# pirmod.net
KiCad netlist of a schematic drawn in EAGLE
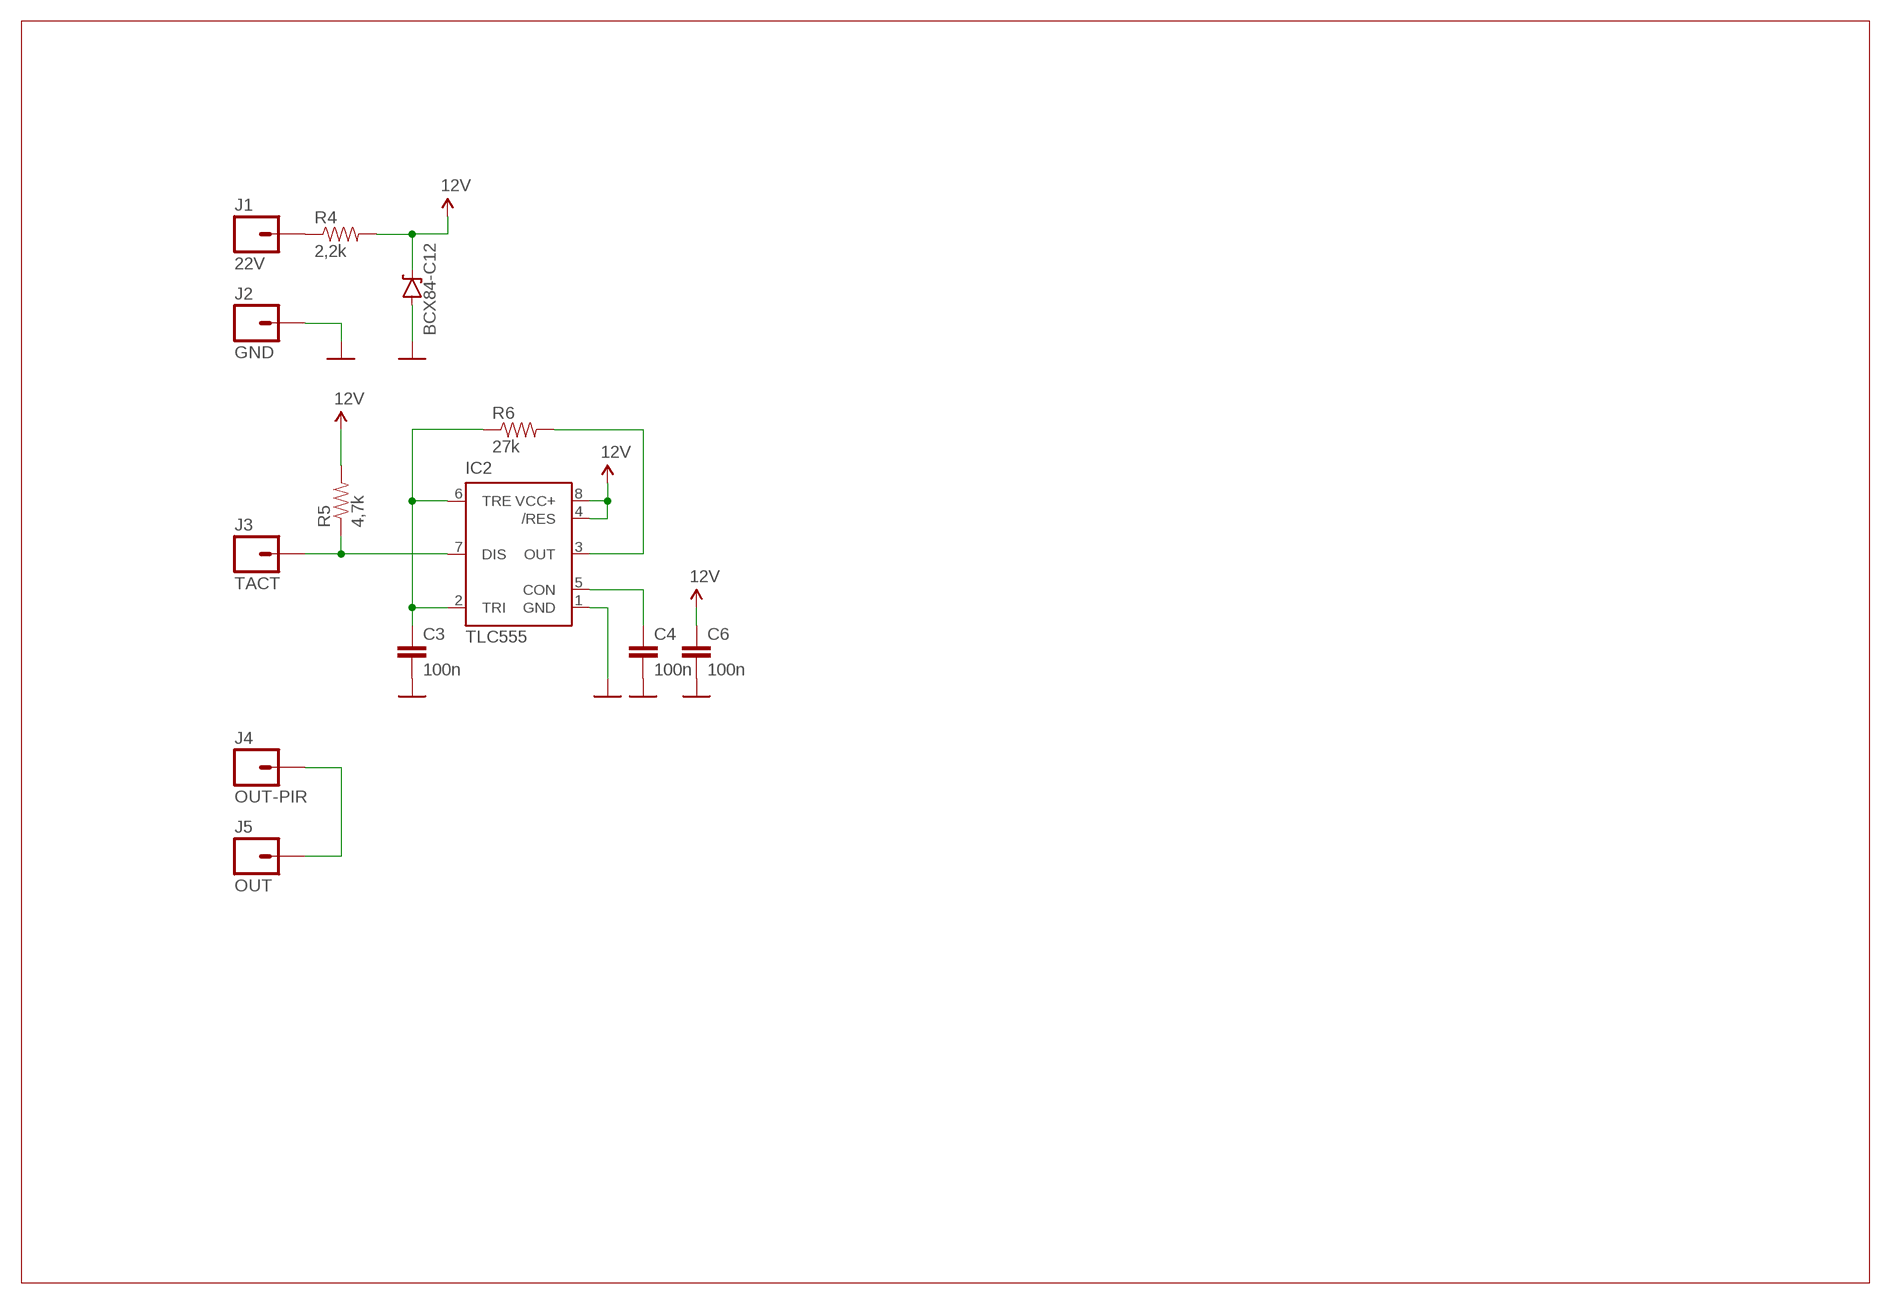
[diagram p0: schematic, sheet 1]

(export (version "E")
  (design (tool "Eeschema 10.0.6"))
  (components
    (comp (ref "C3")
      (value "100n")
      (footprint "eagle-import:0805")
      (libsource (lib "eagle-import") (part "CAP0805"))
    )
    (comp (ref "C4")
      (value "100n")
      (footprint "eagle-import:0805")
      (libsource (lib "eagle-import") (part "CAP0805"))
    )
    (comp (ref "C6")
      (value "100n")
      (footprint "eagle-import:0805")
      (libsource (lib "eagle-import") (part "CAP0805"))
    )
    (comp (ref "D2")
      (value "BCX84-C12")
      (footprint "eagle-import:SOT23-3")
      (libsource (lib "eagle-import") (part "DIODE-ZENER12V"))
    )
    (comp (ref "IC2")
      (value "TLC555")
      (footprint "eagle-import:SO08")
      (libsource (lib "eagle-import") (part "NE555D"))
    )
    (comp (ref "J1")
      (value "22V")
      (footprint "eagle-import:1X01")
      (libsource (lib "eagle-import") (part "M01PTH"))
    )
    (comp (ref "J2")
      (value "GND")
      (footprint "eagle-import:PAD-1.5X4.5")
      (libsource (lib "eagle-import") (part "M01SMD-4.5X1.5"))
    )
    (comp (ref "J3")
      (value "TACT")
      (footprint "eagle-import:1X01")
      (libsource (lib "eagle-import") (part "M01PTH"))
    )
    (comp (ref "J4")
      (value "OUT-PIR")
      (footprint "eagle-import:1X01")
      (libsource (lib "eagle-import") (part "M01PTH"))
    )
    (comp (ref "J5")
      (value "OUT")
      (footprint "eagle-import:1X01")
      (libsource (lib "eagle-import") (part "M01PTH"))
    )
    (comp (ref "R4")
      (value "2,2k")
      (footprint "eagle-import:0805")
      (libsource (lib "eagle-import") (part "RESISTOR0805-RES"))
    )
    (comp (ref "R5")
      (value "4,7k")
      (footprint "eagle-import:0805")
      (libsource (lib "eagle-import") (part "RESISTOR0805-RES"))
    )
    (comp (ref "R6")
      (value "27k")
      (footprint "eagle-import:0805")
      (libsource (lib "eagle-import") (part "RESISTOR0805-RES"))
    )
  )
  (nets
    (net (code "1") (name "12V") (class "Default")
      (node (ref "C6") (pin "1") (pinfunction "1_1") (pintype "passive"))
      (node (ref "D2") (pin "3") (pinfunction "C_3") (pintype "passive"))
      (node (ref "IC2") (pin "4") (pinfunction "/RES_4") (pintype "input"))
      (node (ref "IC2") (pin "8") (pinfunction "VCC+_8") (pintype "power_in"))
      (node (ref "R4") (pin "2") (pinfunction "2_2") (pintype "passive"))
      (node (ref "R5") (pin "2") (pinfunction "2_2") (pintype "passive"))
    )
    (net (code "2") (name "GND") (class "Default")
      (node (ref "C3") (pin "2") (pinfunction "2_2") (pintype "passive"))
      (node (ref "C4") (pin "2") (pinfunction "2_2") (pintype "passive"))
      (node (ref "C6") (pin "2") (pinfunction "2_2") (pintype "passive"))
      (node (ref "D2") (pin "1") (pinfunction "A_1") (pintype "passive"))
      (node (ref "IC2") (pin "1") (pinfunction "GND_1") (pintype "power_in"))
      (node (ref "J2") (pin "P$1") (pinfunction "1_P$1") (pintype "passive"))
    )
    (net (code "3") (name "Net-(IC2-CON)") (class "Default")
      (node (ref "C4") (pin "1") (pinfunction "1_1") (pintype "passive"))
      (node (ref "IC2") (pin "5") (pinfunction "CON_5") (pintype "input"))
    )
    (net (code "4") (name "Net-(IC2-DIS)") (class "Default")
      (node (ref "IC2") (pin "7") (pinfunction "DIS_7") (pintype "input"))
      (node (ref "J3") (pin "1") (pinfunction "1_1") (pintype "passive"))
      (node (ref "R5") (pin "1") (pinfunction "1_1") (pintype "passive"))
    )
    (net (code "5") (name "Net-(IC2-OUT)") (class "Default")
      (node (ref "IC2") (pin "3") (pinfunction "OUT_3") (pintype "output"))
      (node (ref "R6") (pin "2") (pinfunction "2_2") (pintype "passive"))
    )
    (net (code "6") (name "Net-(IC2-TRE)") (class "Default")
      (node (ref "C3") (pin "1") (pinfunction "1_1") (pintype "passive"))
      (node (ref "IC2") (pin "2") (pinfunction "TRI_2") (pintype "input"))
      (node (ref "IC2") (pin "6") (pinfunction "TRE_6") (pintype "input"))
      (node (ref "R6") (pin "1") (pinfunction "1_1") (pintype "passive"))
    )
    (net (code "7") (name "Net-(J1-Pad1)") (class "Default")
      (node (ref "J1") (pin "1") (pinfunction "1_1") (pintype "passive"))
      (node (ref "R4") (pin "1") (pinfunction "1_1") (pintype "passive"))
    )
    (net (code "8") (name "Net-(J4-Pad1)") (class "Default")
      (node (ref "J4") (pin "1") (pinfunction "1_1") (pintype "passive"))
      (node (ref "J5") (pin "1") (pinfunction "1_1") (pintype "passive"))
    )
  )
)
